# Pithy_Dial.net
KiCad netlist of a schematic drawn in EAGLE
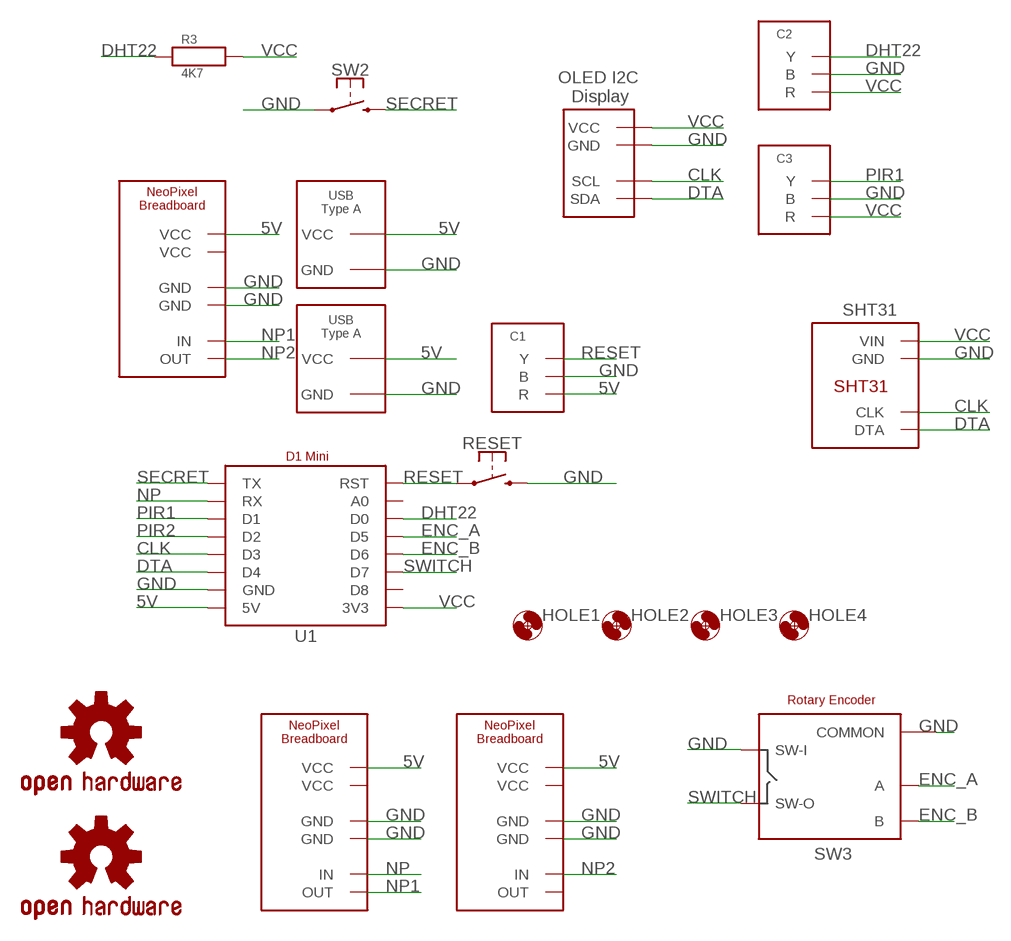
[diagram p0: schematic, sheet 1]

(export (version "E")
  (design (tool "Eeschema 10.0.6"))
  (components
    (comp (ref "C1")
      (value "JST_2MM_3PIN")
      (footprint "eagle-import:JST_2MM_3PIN")
      (libsource (lib "eagle-import") (part "JST_2MM_3PIN"))
    )
    (comp (ref "C2")
      (value "JST_2MM_3PIN")
      (footprint "eagle-import:JST_2MM_3PIN")
      (libsource (lib "eagle-import") (part "JST_2MM_3PIN"))
    )
    (comp (ref "C3")
      (value "JST_2MM_3PIN")
      (footprint "eagle-import:JST_2MM_3PIN")
      (libsource (lib "eagle-import") (part "JST_2MM_3PIN"))
    )
    (comp (ref "HOLE1")
      (value "HOLE_3.2")
      (footprint "eagle-import:HOLE_3.2")
      (libsource (lib "eagle-import") (part "HOLE_3.2"))
    )
    (comp (ref "HOLE2")
      (value "HOLE_3.2")
      (footprint "eagle-import:HOLE_3.2")
      (libsource (lib "eagle-import") (part "HOLE_3.2"))
    )
    (comp (ref "HOLE3")
      (value "HOLE_3.2")
      (footprint "eagle-import:HOLE_3.2")
      (libsource (lib "eagle-import") (part "HOLE_3.2"))
    )
    (comp (ref "HOLE4")
      (value "HOLE_3.2")
      (footprint "eagle-import:HOLE_3.2")
      (libsource (lib "eagle-import") (part "HOLE_3.2"))
    )
    (comp (ref "LOGO1")
      (value "OSHW-LOGOM")
      (footprint "eagle-import:OSHW-LOGO-M")
      (libsource (lib "eagle-import") (part "OSHW-LOGOM"))
    )
    (comp (ref "LOGO2")
      (value "OSHW-LOGOS")
      (footprint "eagle-import:OSHW-LOGO-S")
      (libsource (lib "eagle-import") (part "OSHW-LOGOS"))
    )
    (comp (ref "NP1")
      (value "NEOPIXEL_BREADBOARD")
      (footprint "eagle-import:NEOPIXEL_BREADBOARD")
      (libsource (lib "eagle-import") (part "NEOPIXEL_BREADBOARD"))
    )
    (comp (ref "NP2")
      (value "LEFT_NEOPIXEL")
      (footprint "eagle-import:NEOPIXEL_BREADBOARD")
      (libsource (lib "eagle-import") (part "NEOPIXEL_BREADBOARD"))
    )
    (comp (ref "NP3")
      (value "RIGHT_NEOPIXEL")
      (footprint "eagle-import:NEOPIXEL_BREADBOARD")
      (libsource (lib "eagle-import") (part "NEOPIXEL_BREADBOARD"))
    )
    (comp (ref "R3")
      (value "4K7")
      (footprint "eagle-import:1_4W_RESISTOR")
      (libsource (lib "eagle-import") (part "1/4W_RESISTOR"))
    )
    (comp (ref "RESET")
      (value "SPDT_MOMENTARY")
      (footprint "eagle-import:SPDT_RIGHT_ANGLE")
      (libsource (lib "eagle-import") (part "SPDT_MOMENTARY"))
    )
    (comp (ref "SHT31")
      (value "SHT31RIGHT_ANGLED")
      (footprint "eagle-import:SHT31_RIGHT_ANGLE")
      (libsource (lib "eagle-import") (part "SHT31RIGHT_ANGLED"))
    )
    (comp (ref "SW2")
      (value "SPDT_MOMENTARY")
      (footprint "eagle-import:SPDT_RIGHT_ANGLE")
      (libsource (lib "eagle-import") (part "SPDT_MOMENTARY"))
    )
    (comp (ref "SW3")
      (value "ENCODER")
      (footprint "eagle-import:ROTARY_ENCODER")
      (libsource (lib "eagle-import") (part "ROTARY_ENCODER"))
    )
    (comp (ref "U$1")
      (value "USB_TYPE_A")
      (footprint "eagle-import:USB_TYPE_A_BACKWARDS")
      (libsource (lib "eagle-import") (part "USB_TYPE_A"))
    )
    (comp (ref "U$3")
      (value "USB_TYPE_A")
      (footprint "eagle-import:USB_TYPE_A_BACKWARDS")
      (libsource (lib "eagle-import") (part "USB_TYPE_A"))
    )
    (comp (ref "U1")
      (value "D1_MINI")
      (footprint "eagle-import:D1_MINI")
      (libsource (lib "eagle-import") (part "D1_MINI"))
    )
    (comp (ref "U2")
      (value "OLED_I2C_0.9\"VCC_LEFT")
      (footprint "eagle-import:OLED_I2C_0.9__ALT")
      (libsource (lib "eagle-import") (part "OLED_I2C_0.9{dblquote}VCC_LEFT"))
    )
  )
  (nets
    (net (code "1") (name "/5V") (class "Default")
      (node (ref "C1") (pin "RED") (pinfunction "R_RED") (pintype "bidirectional"))
      (node (ref "NP1") (pin "VCC") (pinfunction "VCC_VCC") (pintype "bidirectional"))
      (node (ref "NP2") (pin "VCC") (pinfunction "VCC_VCC") (pintype "bidirectional"))
      (node (ref "NP3") (pin "VCC") (pinfunction "VCC_VCC") (pintype "bidirectional"))
      (node (ref "U$1") (pin "VCC") (pinfunction "VCC_VCC") (pintype "bidirectional"))
      (node (ref "U$3") (pin "VCC") (pinfunction "VCC_VCC") (pintype "bidirectional"))
      (node (ref "U1") (pin "5V") (pinfunction "5V_5V") (pintype "bidirectional"))
    )
    (net (code "2") (name "/CLK") (class "Default")
      (node (ref "SHT31") (pin "CLK") (pinfunction "CLK_CLK") (pintype "bidirectional"))
      (node (ref "U1") (pin "D3") (pinfunction "D3_D3") (pintype "bidirectional"))
      (node (ref "U2") (pin "SCL") (pinfunction "SCL_SCL") (pintype "bidirectional"))
    )
    (net (code "3") (name "/DHT22") (class "Default")
      (node (ref "C2") (pin "YELLOW") (pinfunction "Y_YELLOW") (pintype "bidirectional"))
      (node (ref "R3") (pin "P$1") (pinfunction "P$1_P$1") (pintype "passive"))
      (node (ref "U1") (pin "D0") (pinfunction "D0_D0") (pintype "bidirectional"))
    )
    (net (code "4") (name "/DTA") (class "Default")
      (node (ref "SHT31") (pin "DTA") (pinfunction "DTA_DTA") (pintype "bidirectional"))
      (node (ref "U1") (pin "D4") (pinfunction "D4_D4") (pintype "bidirectional"))
      (node (ref "U2") (pin "SDA") (pinfunction "SDA_SDA") (pintype "bidirectional"))
    )
    (net (code "5") (name "/ENC_A") (class "Default")
      (node (ref "SW3") (pin "A") (pinfunction "A_A") (pintype "output"))
      (node (ref "U1") (pin "D5") (pinfunction "D5_D5") (pintype "bidirectional"))
    )
    (net (code "6") (name "/ENC_B") (class "Default")
      (node (ref "SW3") (pin "B") (pinfunction "B_B") (pintype "output"))
      (node (ref "U1") (pin "D6") (pinfunction "D6_D6") (pintype "bidirectional"))
    )
    (net (code "7") (name "/GND") (class "Default")
      (node (ref "C1") (pin "BLACK") (pinfunction "B_BLACK") (pintype "bidirectional"))
      (node (ref "C2") (pin "BLACK") (pinfunction "B_BLACK") (pintype "bidirectional"))
      (node (ref "C3") (pin "BLACK") (pinfunction "B_BLACK") (pintype "bidirectional"))
      (node (ref "NP1") (pin "GND") (pinfunction "GND_GND") (pintype "bidirectional"))
      (node (ref "NP1") (pin "GND@2") (pinfunction "GND_GND@2") (pintype "bidirectional"))
      (node (ref "NP2") (pin "GND") (pinfunction "GND_GND") (pintype "bidirectional"))
      (node (ref "NP2") (pin "GND@2") (pinfunction "GND_GND@2") (pintype "bidirectional"))
      (node (ref "NP3") (pin "GND") (pinfunction "GND_GND") (pintype "bidirectional"))
      (node (ref "NP3") (pin "GND@2") (pinfunction "GND_GND@2") (pintype "bidirectional"))
      (node (ref "RESET") (pin "2") (pinfunction "3_2") (pintype "passive"))
      (node (ref "SHT31") (pin "GND") (pinfunction "GND_GND") (pintype "bidirectional"))
      (node (ref "SW2") (pin "1") (pinfunction "1_1") (pintype "passive"))
      (node (ref "SW3") (pin "C") (pinfunction "COMMON_C") (pintype "input"))
      (node (ref "SW3") (pin "SW+") (pinfunction "SW-I_SW+") (pintype "input"))
      (node (ref "U$1") (pin "GND") (pinfunction "GND_GND") (pintype "bidirectional"))
      (node (ref "U$3") (pin "GND") (pinfunction "GND_GND") (pintype "bidirectional"))
      (node (ref "U1") (pin "GND") (pinfunction "GND_GND") (pintype "bidirectional"))
      (node (ref "U2") (pin "GND") (pinfunction "GND_GND") (pintype "power_in"))
    )
    (net (code "8") (name "/NP") (class "Default")
      (node (ref "NP2") (pin "IN") (pinfunction "IN_IN") (pintype "bidirectional"))
      (node (ref "U1") (pin "RX") (pinfunction "RX_RX") (pintype "bidirectional"))
    )
    (net (code "9") (name "/NP1") (class "Default")
      (node (ref "NP1") (pin "IN") (pinfunction "IN_IN") (pintype "bidirectional"))
      (node (ref "NP2") (pin "OUT") (pinfunction "OUT_OUT") (pintype "bidirectional"))
    )
    (net (code "10") (name "/NP2") (class "Default")
      (node (ref "NP1") (pin "OUT") (pinfunction "OUT_OUT") (pintype "bidirectional"))
      (node (ref "NP3") (pin "IN") (pinfunction "IN_IN") (pintype "bidirectional"))
    )
    (net (code "11") (name "/PIR1") (class "Default")
      (node (ref "C3") (pin "YELLOW") (pinfunction "Y_YELLOW") (pintype "bidirectional"))
      (node (ref "U1") (pin "D1") (pinfunction "D1_D1") (pintype "bidirectional"))
    )
    (net (code "12") (name "/PIR2") (class "Default")
      (node (ref "U1") (pin "D2") (pinfunction "D2_D2") (pintype "bidirectional"))
    )
    (net (code "13") (name "/RESET") (class "Default")
      (node (ref "C1") (pin "YELLOW") (pinfunction "Y_YELLOW") (pintype "bidirectional"))
      (node (ref "RESET") (pin "1") (pinfunction "1_1") (pintype "passive"))
      (node (ref "U1") (pin "RST") (pinfunction "RST_RST") (pintype "bidirectional"))
    )
    (net (code "14") (name "/SECRET") (class "Default")
      (node (ref "SW2") (pin "2") (pinfunction "3_2") (pintype "passive"))
      (node (ref "U1") (pin "TX") (pinfunction "TX_TX") (pintype "bidirectional"))
    )
    (net (code "15") (name "/SWITCH") (class "Default")
      (node (ref "SW3") (pin "SW-") (pinfunction "SW-O_SW-") (pintype "output"))
      (node (ref "U1") (pin "D7") (pinfunction "D7_D7") (pintype "bidirectional"))
    )
    (net (code "16") (name "/VCC") (class "Default")
      (node (ref "C2") (pin "RED") (pinfunction "R_RED") (pintype "bidirectional"))
      (node (ref "C3") (pin "RED") (pinfunction "R_RED") (pintype "bidirectional"))
      (node (ref "R3") (pin "P$2") (pinfunction "P$2_P$2") (pintype "passive"))
      (node (ref "SHT31") (pin "VIN") (pinfunction "VIN_VIN") (pintype "bidirectional"))
      (node (ref "U1") (pin "3V3") (pinfunction "3V3_3V3") (pintype "bidirectional"))
      (node (ref "U2") (pin "VCC") (pinfunction "VCC_VCC") (pintype "power_in"))
    )
    (net (code "17") (name "unconnected-(NP1-VCC-PadVCC@2)") (class "Default")
      (node (ref "NP1") (pin "VCC@2") (pinfunction "VCC_VCC@2") (pintype "bidirectional"))
    )
    (net (code "18") (name "unconnected-(NP2-VCC-PadVCC@2)") (class "Default")
      (node (ref "NP2") (pin "VCC@2") (pinfunction "VCC_VCC@2") (pintype "bidirectional"))
    )
    (net (code "19") (name "unconnected-(NP3-PadOUT)") (class "Default")
      (node (ref "NP3") (pin "OUT") (pinfunction "OUT_OUT") (pintype "bidirectional"))
    )
    (net (code "20") (name "unconnected-(NP3-VCC-PadVCC@2)") (class "Default")
      (node (ref "NP3") (pin "VCC@2") (pinfunction "VCC_VCC@2") (pintype "bidirectional"))
    )
    (net (code "21") (name "unconnected-(U1-PadA0)") (class "Default")
      (node (ref "U1") (pin "A0") (pinfunction "A0_A0") (pintype "bidirectional"))
    )
    (net (code "22") (name "unconnected-(U1-PadD8)") (class "Default")
      (node (ref "U1") (pin "D8") (pinfunction "D8_D8") (pintype "bidirectional"))
    )
  )
)
